# sheet1.net
KiCad netlist of a schematic drawn in Altium Designer
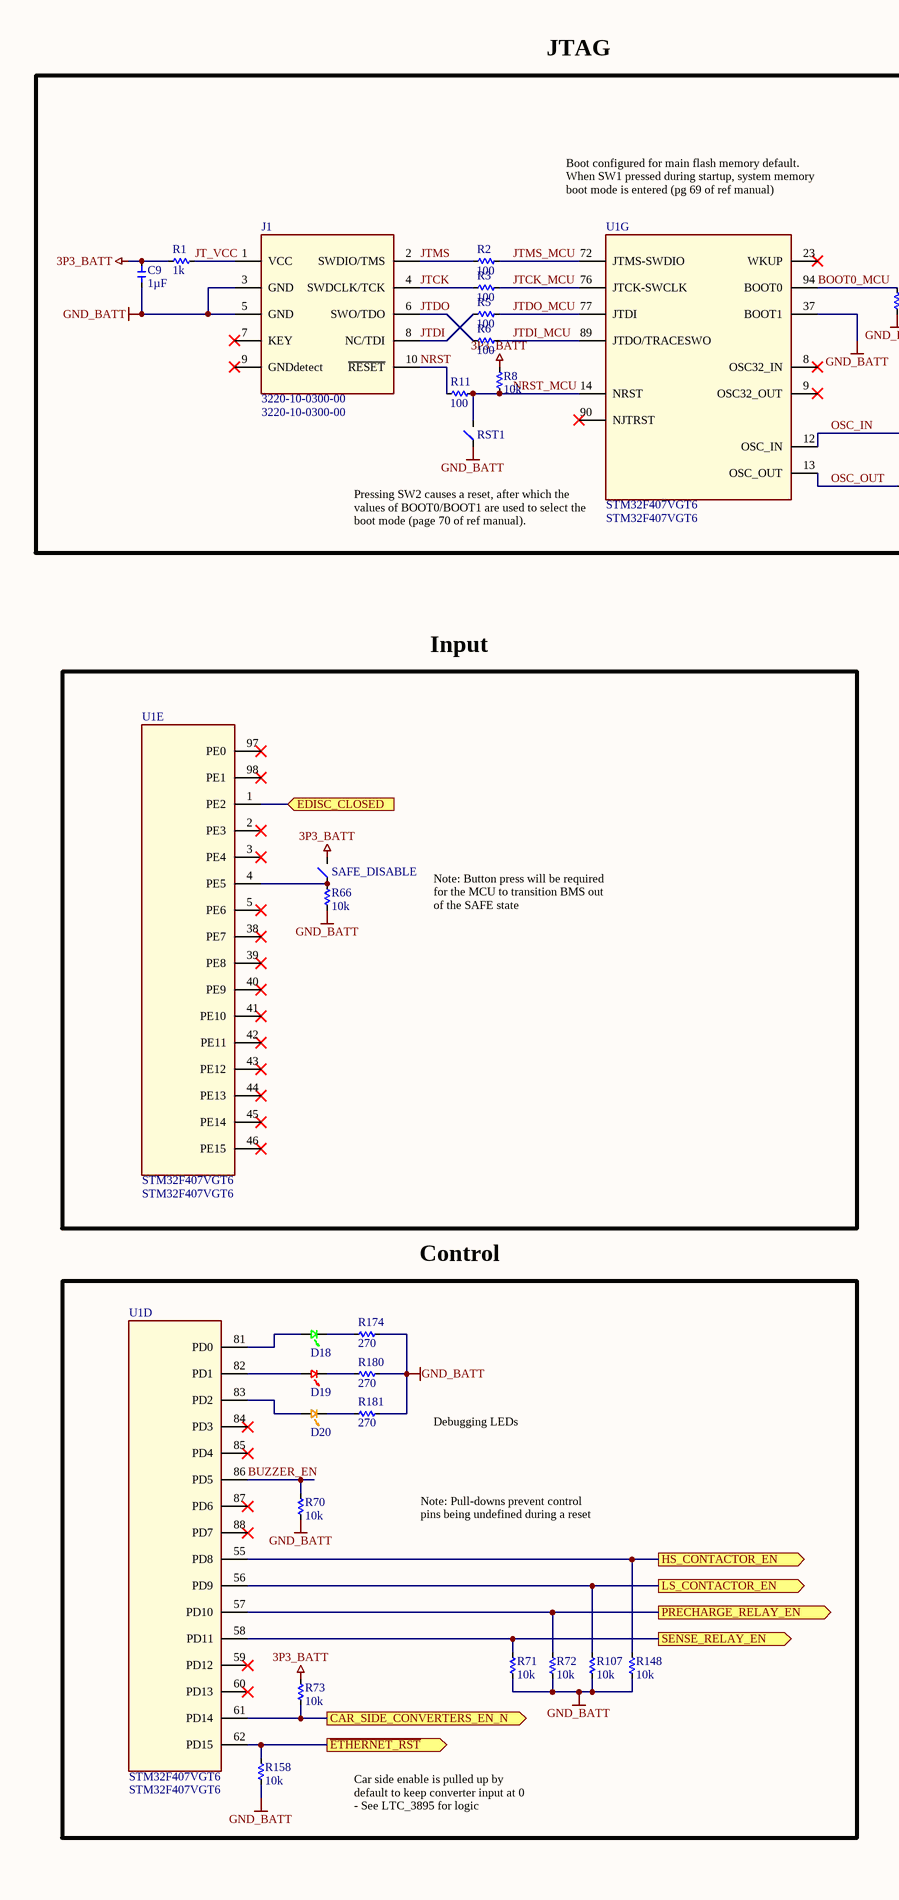
[diagram p0: sheet1.SchDoc, left]
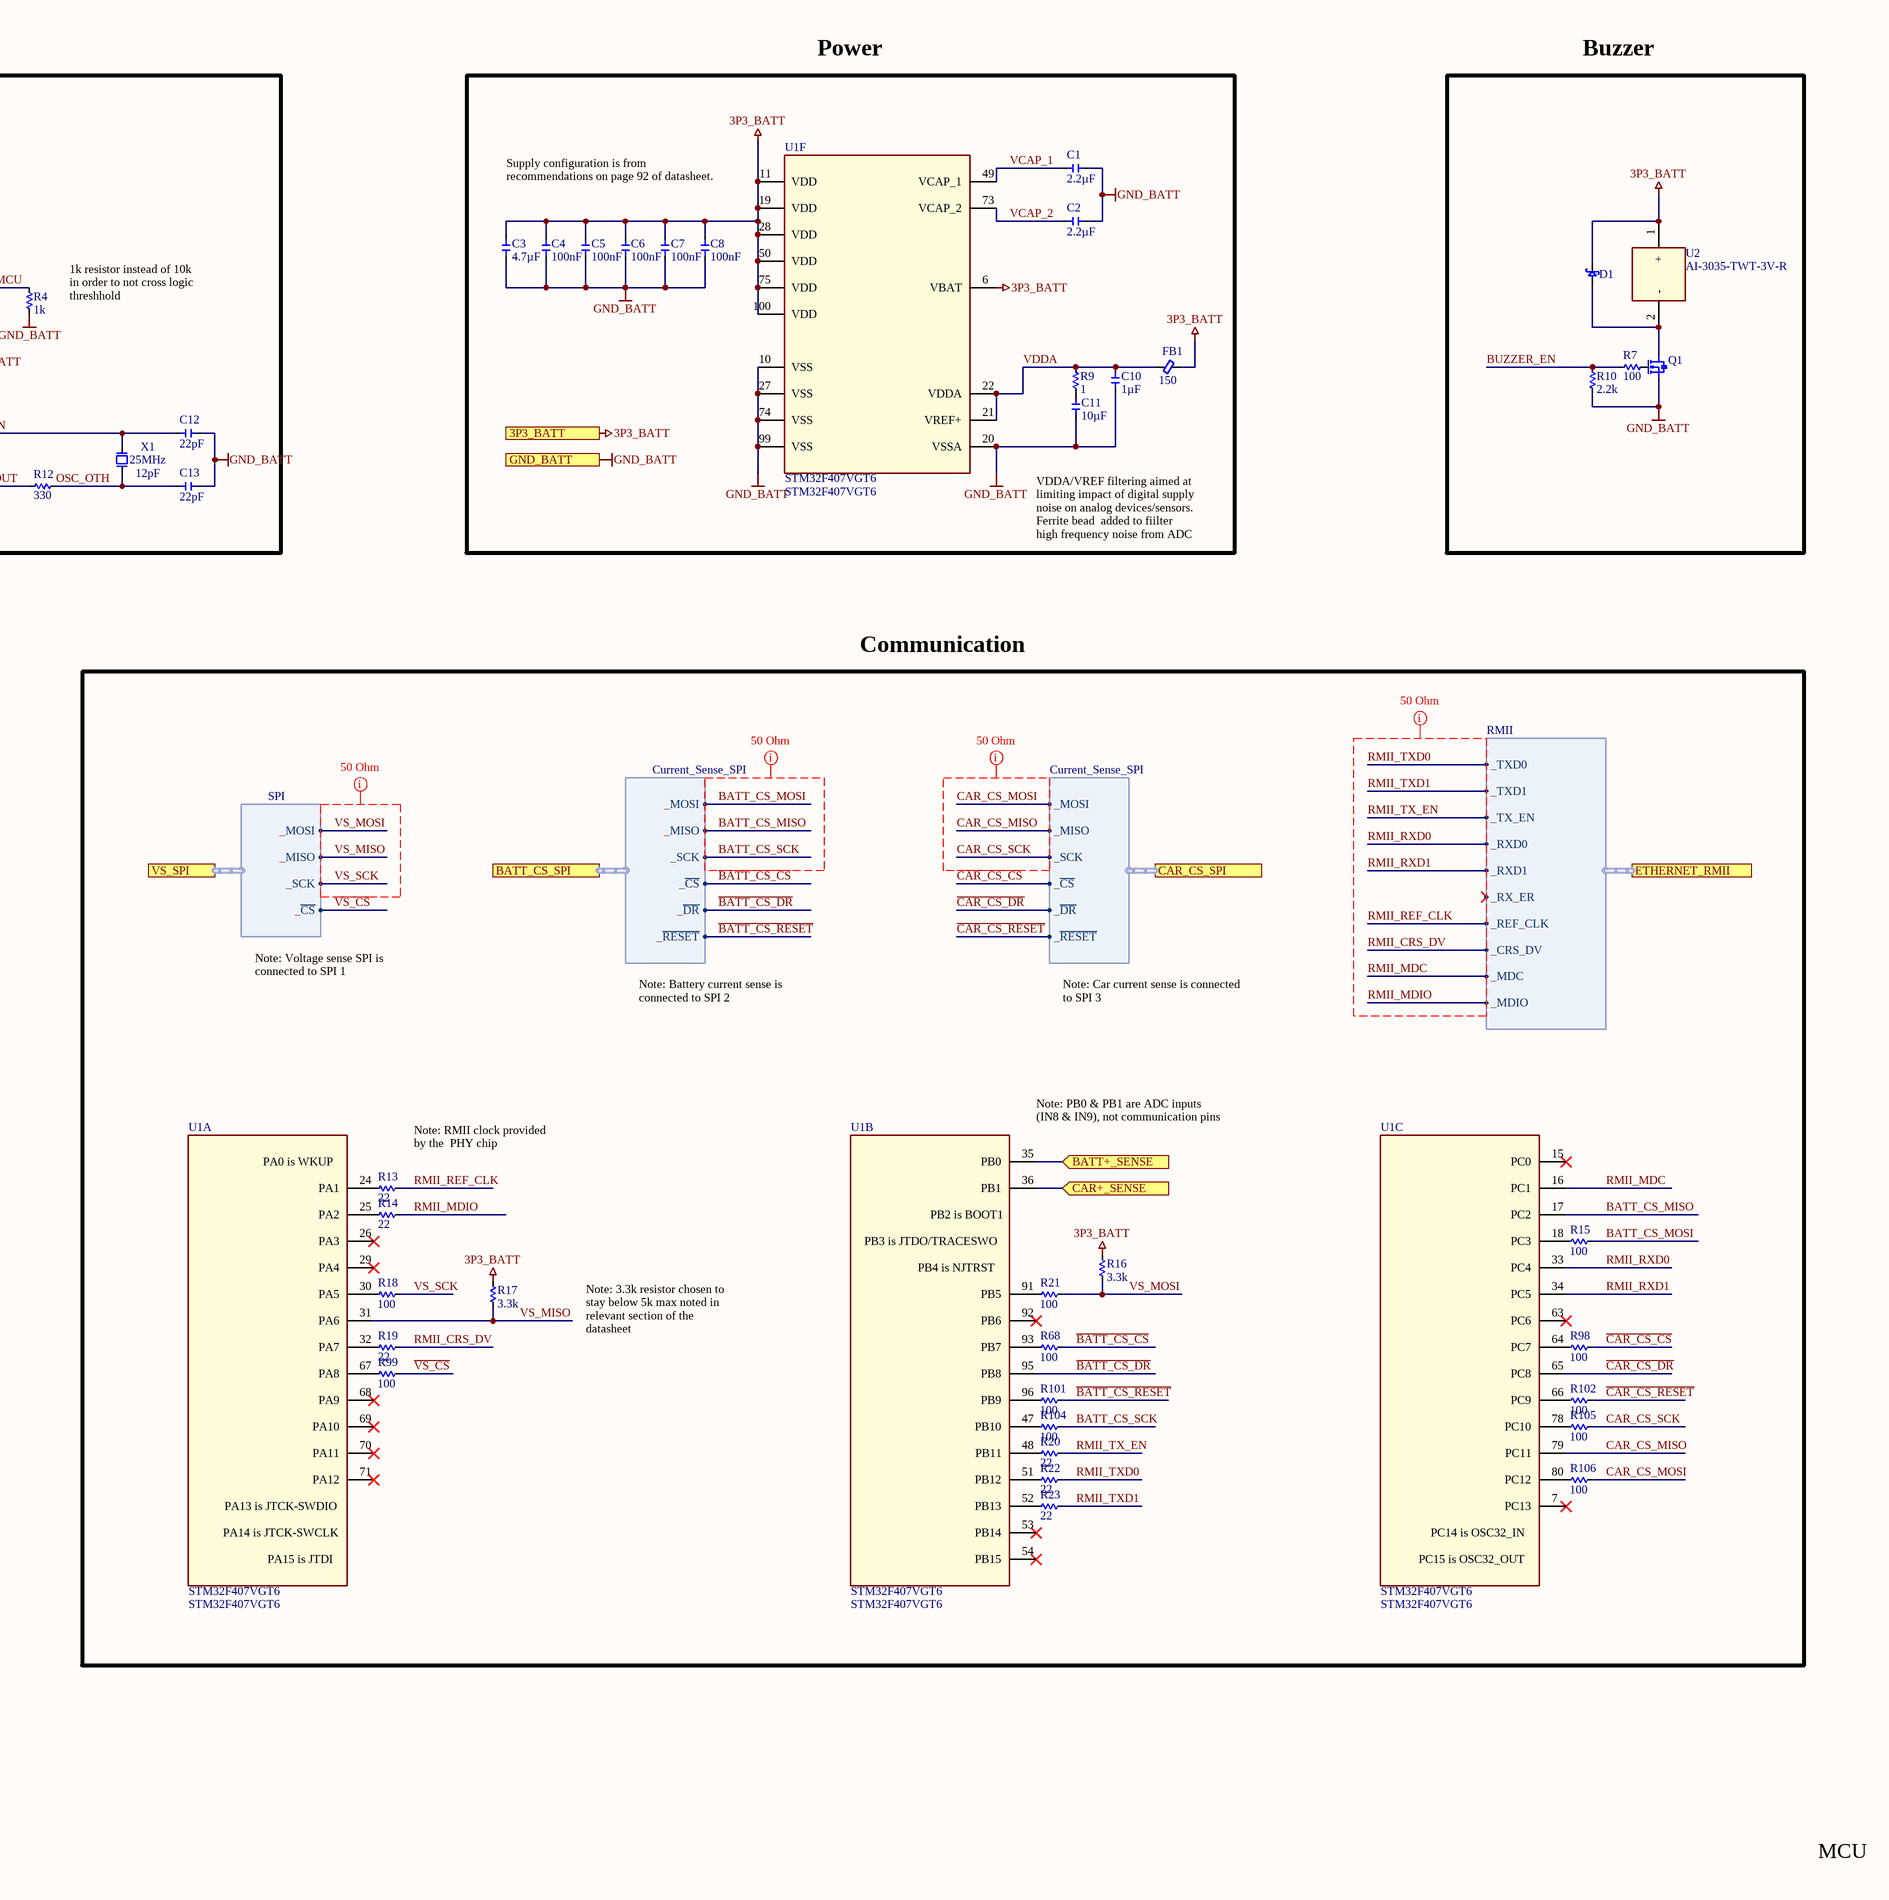
[diagram p1: sheet1.SchDoc, right]

(export (version "E")
  (design (tool "Eeschema 10.0.6"))
  (components
    (comp (ref "C1")
      (value "2.2µF")
      (footprint "C0603_0.90MM")
      (description "CAP CER 2.2UF 16V X7S 0603")
      (fields (field (name "TOLERANCE") "10%") (field (name "DIGI-KEY PART NUMBER") "445-16104-1-ND"))
      (libsource (lib "Stanford Solar Car Project") (part "2pin_nonpolar_capacitor"))
    )
    (comp (ref "C2")
      (value "2.2µF")
      (footprint "C0603_0.90MM")
      (description "CAP CER 2.2UF 16V X7S 0603")
      (fields (field (name "TOLERANCE") "10%") (field (name "DIGI-KEY PART NUMBER") "445-16104-1-ND"))
      (libsource (lib "Stanford Solar Car Project") (part "2pin_nonpolar_capacitor"))
    )
    (comp (ref "C3")
      (value "4.7µF")
      (footprint "C0805_1.45MM")
      (description "CAP CER 4.7UF 16V X7R 0805")
      (fields
        (field (name "MANUFACTURER") "TDK Corporation")
        (field (name "MANUFACTURER PART NUMBER") "CGA4J3X7R1C475K125AB")
      )
      (libsource (lib "Stanford Solar Car Project") (part "2pin_nonpolar_capacitor"))
    )
    (comp (ref "C4")
      (value "100nF")
      (footprint "C0603_0.90MM")
      (description "CAP CER 0.1UF 50V X7R 0603")
      (fields (field (name "DIGI-KEY PART NUMBER") "445-5666-1-ND") (field (name "TOLERANCE") "10%"))
      (libsource (lib "Stanford Solar Car Project") (part "2pin_nonpolar_capacitor"))
    )
    (comp (ref "C5")
      (value "100nF")
      (footprint "C0603_0.90MM")
      (description "CAP CER 0.1UF 50V X7R 0603")
      (fields (field (name "DIGI-KEY PART NUMBER") "445-5666-1-ND") (field (name "TOLERANCE") "10%"))
      (libsource (lib "Stanford Solar Car Project") (part "2pin_nonpolar_capacitor"))
    )
    (comp (ref "C6")
      (value "100nF")
      (footprint "C0603_0.90MM")
      (description "CAP CER 0.1UF 50V X7R 0603")
      (fields (field (name "DIGI-KEY PART NUMBER") "445-5666-1-ND") (field (name "TOLERANCE") "10%"))
      (libsource (lib "Stanford Solar Car Project") (part "2pin_nonpolar_capacitor"))
    )
    (comp (ref "C7")
      (value "100nF")
      (footprint "C0603_0.90MM")
      (description "CAP CER 0.1UF 50V X7R 0603")
      (fields (field (name "DIGI-KEY PART NUMBER") "445-5666-1-ND") (field (name "TOLERANCE") "10%"))
      (libsource (lib "Stanford Solar Car Project") (part "2pin_nonpolar_capacitor"))
    )
    (comp (ref "C8")
      (value "100nF")
      (footprint "C0603_0.90MM")
      (description "CAP CER 0.1UF 50V X7R 0603")
      (fields (field (name "DIGI-KEY PART NUMBER") "445-5666-1-ND") (field (name "TOLERANCE") "10%"))
      (libsource (lib "Stanford Solar Car Project") (part "2pin_nonpolar_capacitor"))
    )
    (comp (ref "C9")
      (value "1µF")
      (footprint "C0805_1.50MM")
      (description "CAP CER 1UF 50V X7R 0805")
      (fields
        (field (name "MANUFACTURER") "TDK Corporation")
        (field (name "DIGI-KEY PART NUMBER") "445-6961-1-ND")
      )
      (libsource (lib "Stanford Solar Car Project") (part "2pin_nonpolar_capacitor"))
    )
    (comp (ref "C10")
      (value "1µF")
      (footprint "C0805_1.50MM")
      (description "CAP CER 1UF 50V X7R 0805")
      (fields
        (field (name "MANUFACTURER") "TDK Corporation")
        (field (name "DIGI-KEY PART NUMBER") "445-6961-1-ND")
      )
      (libsource (lib "Stanford Solar Car Project") (part "2pin_nonpolar_capacitor"))
    )
    (comp (ref "C11")
      (value "10µF")
      (footprint "C1210_2.80MM")
      (description "CAP CER 10UF 25V X7R 1210")
      (fields
        (field (name "MANUFACTURER") "TDK Corporation")
        (field (name "MANUFACTURER PART NUMBER") "CGA6P1X7R1E106K250AC")
      )
      (libsource (lib "Stanford Solar Car Project") (part "2pin_nonpolar_capacitor"))
    )
    (comp (ref "C12")
      (value "22pF")
      (footprint "C0603_0.90MM")
      (description "CAP CER 22PF 50V C0G 0603")
      (fields (field (name "TOLERANCE") "5%") (field (name "DIGI-KEY PART NUMBER") "445-5632-1-ND"))
      (libsource (lib "Stanford Solar Car Project") (part "2pin_nonpolar_capacitor"))
    )
    (comp (ref "C13")
      (value "22pF")
      (footprint "C0603_0.90MM")
      (description "CAP CER 22PF 50V C0G 0603")
      (fields (field (name "TOLERANCE") "5%") (field (name "DIGI-KEY PART NUMBER") "445-5632-1-ND"))
      (libsource (lib "Stanford Solar Car Project") (part "2pin_nonpolar_capacitor"))
    )
    (comp (ref "D1")
      (value "DFLS130L-7")
      (footprint "DIOD-POWERDI123-2_A_V")
      (libsource (lib "Stanford Solar Car Project") (part "_template_schottky"))
    )
    (comp (ref "D18")
      (value "LTST-C191KGKT")
      (footprint "LED_0603P_GREEN")
      (description "LED GREEN CLEAR SMD")
      (fields
        (field (name "MANUFACTURER") "Lite-On Inc.")
        (field (name "DIGI-KEY PART NUMBER") "160-1446-6-ND")
      )
      (libsource (lib "Stanford Solar Car Project") (part "_template_led_green"))
    )
    (comp (ref "D19")
      (value "LTST-C194KRKT")
      (footprint "LED_0603P_RED")
      (description "LED RED CLEAR SMD")
      (fields
        (field (name "DIGI-KEY PART NUMBER") "160-1835-6-ND")
        (field (name "MANUFACTURER") "Lite-On Inc.")
      )
      (libsource (lib "Stanford Solar Car Project") (part "_template_led_red"))
    )
    (comp (ref "D20")
      (value "LTST-C194KFKT")
      (footprint "LED_0603P_ORANGE")
      (description "LED ORANGE CLEAR SMD")
      (libsource (lib "Stanford Solar Car Project") (part "_template_led_orange"))
    )
    (comp (ref "FB1")
      (value "MPZ1608Y151BTD25")
      (footprint "FB0603_0.95MM")
      (description "FERRITE BEAD 150 OHM 0603 1LN")
      (fields
        (field (name "DIGI-KEY PART NUMBER") "445-172900-1-ND")
        (field (name "IMPEDANCE (OHMS @ 100MHZ)") "150")
        (field (name "MANUFACTURER") "TDK Corporation")
      )
      (libsource (lib "Stanford Solar Car Project") (part "2pin_ferritebead"))
    )
    (comp (ref "J1")
      (value "3220-10-0300-00")
      (footprint "3220-10-0300-00")
      (description "CONN HEADER SMD 10POS 1.27MM")
      (fields
        (field (name "MANUFACTURER PART NUMBER") "3220-10-0300-00")
        (field (name "MANUFACTURER") "CNC Tech")
        (field (name "DIGI-KEY PART NUMBER") "1175-1629-ND")
      )
      (libsource (lib "Stanford Solar Car Project") (part "CONN_3220-10-0300-00"))
    )
    (comp (ref "Q1")
      (value "BSR802NL6327")
      (footprint "3SOT23")
      (description "Infineon BSR802N L6327 N-channel MOSFET Transistor, 3.7 A, 20 V, 3-Pin SC-59")
      (libsource (lib "Stanford Solar Car Project") (part "__template_nfet"))
    )
    (comp (ref "R1")
      (value "1k")
      (footprint "R0603_0.55MM")
      (description "RES SMD 1K OHM 1% 1/4W 0603")
      (fields (field (name "TOLERANCE") "1%") (field (name "DIGI-KEY PART NUMBER") "P1.0KBYCT-ND"))
      (libsource (lib "Stanford Solar Car Project") (part "2pin_resistor"))
    )
    (comp (ref "R2")
      (value "100")
      (footprint "R0603_0.55MM")
      (description "RES SMD 100 OHM 1% 1/10W 0603")
      (fields
        (field (name "MANUFACTURER PART NUMBER") "ERJ-3EKF1000V")
        (field (name "DIGI-KEY PART NUMBER") "P100HCT-ND")
      )
      (libsource (lib "Stanford Solar Car Project") (part "2pin_resistor"))
    )
    (comp (ref "R3")
      (value "100")
      (footprint "R0603_0.55MM")
      (description "RES SMD 100 OHM 1% 1/10W 0603")
      (fields
        (field (name "MANUFACTURER PART NUMBER") "ERJ-3EKF1000V")
        (field (name "DIGI-KEY PART NUMBER") "P100HCT-ND")
      )
      (libsource (lib "Stanford Solar Car Project") (part "2pin_resistor"))
    )
    (comp (ref "R4")
      (value "1k")
      (footprint "R0603_0.55MM")
      (description "RES SMD 1K OHM 1% 1/4W 0603")
      (fields (field (name "TOLERANCE") "1%") (field (name "DIGI-KEY PART NUMBER") "P1.0KBYCT-ND"))
      (libsource (lib "Stanford Solar Car Project") (part "2pin_resistor"))
    )
    (comp (ref "R5")
      (value "100")
      (footprint "R0603_0.55MM")
      (description "RES SMD 100 OHM 1% 1/10W 0603")
      (fields
        (field (name "MANUFACTURER PART NUMBER") "ERJ-3EKF1000V")
        (field (name "DIGI-KEY PART NUMBER") "P100HCT-ND")
      )
      (libsource (lib "Stanford Solar Car Project") (part "2pin_resistor"))
    )
    (comp (ref "R6")
      (value "100")
      (footprint "R0603_0.55MM")
      (description "RES SMD 100 OHM 1% 1/10W 0603")
      (fields
        (field (name "MANUFACTURER PART NUMBER") "ERJ-3EKF1000V")
        (field (name "DIGI-KEY PART NUMBER") "P100HCT-ND")
      )
      (libsource (lib "Stanford Solar Car Project") (part "2pin_resistor"))
    )
    (comp (ref "R7")
      (value "100")
      (footprint "R0603_0.55MM")
      (description "RES SMD 100 OHM 1% 1/4W 0603")
      (fields (field (name "MANUFACTURER PART NUMBER") "ERJ-PA3F1000V") (field (name "TOLERANCE") "1%"))
      (libsource (lib "Stanford Solar Car Project") (part "2pin_resistor"))
    )
    (comp (ref "R8")
      (value "10k")
      (footprint "R0603_0.55MM")
      (description "RES SMD 10K OHM 1% 1/10W 0603")
      (fields
        (field (name "MANUFACTURER PART NUMBER") "ERJ-3EKF1002V")
        (field (name "MANUFACTURER") "Panasonic Electronic Components")
      )
      (libsource (lib "Stanford Solar Car Project") (part "2pin_resistor"))
    )
    (comp (ref "R9")
      (value "1")
      (footprint "R0603_0.55MM")
      (description "RES SMD 1 OHM 1% 1/10W 0603")
      (fields (field (name "TOLERANCE") "1%") (field (name "DIGI-KEY PART NUMBER") "P1.0AJCT-ND"))
      (libsource (lib "Stanford Solar Car Project") (part "2pin_resistor"))
    )
    (comp (ref "R10")
      (value "2.2k")
      (footprint "R0603_0.55MM")
      (description "RES SMD 2.2K OHM 1% 1/4W 0603")
      (fields (field (name "MANUFACTURER") "Panasonic Electronic Components") (field (name "TOLERANCE") "1%"))
      (libsource (lib "Stanford Solar Car Project") (part "2pin_resistor"))
    )
    (comp (ref "R11")
      (value "100")
      (footprint "R0603_0.55MM")
      (description "RES SMD 100 OHM 1% 1/10W 0603")
      (fields
        (field (name "MANUFACTURER PART NUMBER") "ERJ-3EKF1000V")
        (field (name "DIGI-KEY PART NUMBER") "P100HCT-ND")
      )
      (libsource (lib "Stanford Solar Car Project") (part "2pin_resistor"))
    )
    (comp (ref "R12")
      (value "330")
      (footprint "R0603_0.55MM")
      (description "RES SMD 330 OHM 1% 1/10W 0603")
      (fields
        (field (name "DIGI-KEY PART NUMBER") "P330HCT-ND")
        (field (name "MANUFACTURER PART NUMBER") "ERJ-3EKF3300V")
      )
      (libsource (lib "Stanford Solar Car Project") (part "2pin_resistor"))
    )
    (comp (ref "R13")
      (value "22")
      (footprint "R0603_0.55MM")
      (description "RES SMD 22 OHM 1% 1/10W 0603")
      (fields
        (field (name "MANUFACTURER") "Panasonic Electronic Components")
        (field (name "DIGI-KEY PART NUMBER") "P22.0HCT-ND")
      )
      (libsource (lib "Stanford Solar Car Project") (part "2pin_resistor"))
    )
    (comp (ref "R14")
      (value "22")
      (footprint "R0603_0.55MM")
      (description "RES SMD 22 OHM 1% 1/10W 0603")
      (fields
        (field (name "MANUFACTURER") "Panasonic Electronic Components")
        (field (name "DIGI-KEY PART NUMBER") "P22.0HCT-ND")
      )
      (libsource (lib "Stanford Solar Car Project") (part "2pin_resistor"))
    )
    (comp (ref "R15")
      (value "100")
      (footprint "R0603_0.55MM")
      (description "RES SMD 100 OHM 1% 1/10W 0603")
      (fields
        (field (name "MANUFACTURER PART NUMBER") "ERJ-3EKF1000V")
        (field (name "DIGI-KEY PART NUMBER") "P100HCT-ND")
      )
      (libsource (lib "Stanford Solar Car Project") (part "2pin_resistor"))
    )
    (comp (ref "R16")
      (value "3.3k")
      (footprint "R0603_0.55MM")
      (description "RES SMD 3.3K OHM 1% 1/10W 0603")
      (fields
        (field (name "DIGI-KEY PART NUMBER") "P3.30KHCT-ND")
        (field (name "MANUFACTURER") "Panasonic Electronic Components")
      )
      (libsource (lib "Stanford Solar Car Project") (part "2pin_resistor"))
    )
    (comp (ref "R17")
      (value "3.3k")
      (footprint "R0603_0.55MM")
      (description "RES SMD 3.3K OHM 1% 1/10W 0603")
      (fields
        (field (name "DIGI-KEY PART NUMBER") "P3.30KHCT-ND")
        (field (name "MANUFACTURER") "Panasonic Electronic Components")
      )
      (libsource (lib "Stanford Solar Car Project") (part "2pin_resistor"))
    )
    (comp (ref "R18")
      (value "100")
      (footprint "R0603_0.55MM")
      (description "RES SMD 100 OHM 1% 1/10W 0603")
      (fields
        (field (name "MANUFACTURER PART NUMBER") "ERJ-3EKF1000V")
        (field (name "DIGI-KEY PART NUMBER") "P100HCT-ND")
      )
      (libsource (lib "Stanford Solar Car Project") (part "2pin_resistor"))
    )
    (comp (ref "R19")
      (value "22")
      (footprint "R0603_0.55MM")
      (description "RES SMD 22 OHM 1% 1/10W 0603")
      (fields
        (field (name "MANUFACTURER") "Panasonic Electronic Components")
        (field (name "DIGI-KEY PART NUMBER") "P22.0HCT-ND")
      )
      (libsource (lib "Stanford Solar Car Project") (part "2pin_resistor"))
    )
    (comp (ref "R20")
      (value "22")
      (footprint "R0603_0.55MM")
      (description "RES SMD 22 OHM 1% 1/10W 0603")
      (fields
        (field (name "MANUFACTURER") "Panasonic Electronic Components")
        (field (name "DIGI-KEY PART NUMBER") "P22.0HCT-ND")
      )
      (libsource (lib "Stanford Solar Car Project") (part "2pin_resistor"))
    )
    (comp (ref "R21")
      (value "100")
      (footprint "R0603_0.55MM")
      (description "RES SMD 100 OHM 1% 1/10W 0603")
      (fields
        (field (name "MANUFACTURER PART NUMBER") "ERJ-3EKF1000V")
        (field (name "DIGI-KEY PART NUMBER") "P100HCT-ND")
      )
      (libsource (lib "Stanford Solar Car Project") (part "2pin_resistor"))
    )
    (comp (ref "R22")
      (value "22")
      (footprint "R0603_0.55MM")
      (description "RES SMD 22 OHM 1% 1/10W 0603")
      (fields
        (field (name "MANUFACTURER") "Panasonic Electronic Components")
        (field (name "DIGI-KEY PART NUMBER") "P22.0HCT-ND")
      )
      (libsource (lib "Stanford Solar Car Project") (part "2pin_resistor"))
    )
    (comp (ref "R23")
      (value "22")
      (footprint "R0603_0.55MM")
      (description "RES SMD 22 OHM 1% 1/10W 0603")
      (fields
        (field (name "MANUFACTURER") "Panasonic Electronic Components")
        (field (name "DIGI-KEY PART NUMBER") "P22.0HCT-ND")
      )
      (libsource (lib "Stanford Solar Car Project") (part "2pin_resistor"))
    )
    (comp (ref "R66")
      (value "10k")
      (footprint "R0603_0.55MM")
      (description "RES SMD 10K OHM 1% 1/10W 0603")
      (fields
        (field (name "MANUFACTURER PART NUMBER") "ERJ-3EKF1002V")
        (field (name "MANUFACTURER") "Panasonic Electronic Components")
      )
      (libsource (lib "Stanford Solar Car Project") (part "2pin_resistor"))
    )
    (comp (ref "R68")
      (value "100")
      (footprint "R0603_0.55MM")
      (description "RES SMD 100 OHM 1% 1/10W 0603")
      (fields
        (field (name "MANUFACTURER PART NUMBER") "ERJ-3EKF1000V")
        (field (name "DIGI-KEY PART NUMBER") "P100HCT-ND")
      )
      (libsource (lib "Stanford Solar Car Project") (part "2pin_resistor"))
    )
    (comp (ref "R70")
      (value "10k")
      (footprint "R0603_0.55MM")
      (description "RES SMD 10K OHM 1% 1/10W 0603")
      (fields
        (field (name "MANUFACTURER PART NUMBER") "ERJ-3EKF1002V")
        (field (name "MANUFACTURER") "Panasonic Electronic Components")
      )
      (libsource (lib "Stanford Solar Car Project") (part "2pin_resistor"))
    )
    (comp (ref "R71")
      (value "10k")
      (footprint "R0603_0.55MM")
      (description "RES SMD 10K OHM 1% 1/10W 0603")
      (fields
        (field (name "MANUFACTURER PART NUMBER") "ERJ-3EKF1002V")
        (field (name "MANUFACTURER") "Panasonic Electronic Components")
      )
      (libsource (lib "Stanford Solar Car Project") (part "2pin_resistor"))
    )
    (comp (ref "R72")
      (value "10k")
      (footprint "R0603_0.55MM")
      (description "RES SMD 10K OHM 1% 1/10W 0603")
      (fields
        (field (name "MANUFACTURER PART NUMBER") "ERJ-3EKF1002V")
        (field (name "MANUFACTURER") "Panasonic Electronic Components")
      )
      (libsource (lib "Stanford Solar Car Project") (part "2pin_resistor"))
    )
    (comp (ref "R73")
      (value "10k")
      (footprint "R0603_0.55MM")
      (description "RES SMD 10K OHM 1% 1/10W 0603")
      (fields
        (field (name "MANUFACTURER PART NUMBER") "ERJ-3EKF1002V")
        (field (name "MANUFACTURER") "Panasonic Electronic Components")
      )
      (libsource (lib "Stanford Solar Car Project") (part "2pin_resistor"))
    )
    (comp (ref "R98")
      (value "100")
      (footprint "R0603_0.55MM")
      (description "RES SMD 100 OHM 1% 1/10W 0603")
      (fields
        (field (name "MANUFACTURER PART NUMBER") "ERJ-3EKF1000V")
        (field (name "DIGI-KEY PART NUMBER") "P100HCT-ND")
      )
      (libsource (lib "Stanford Solar Car Project") (part "2pin_resistor"))
    )
    (comp (ref "R99")
      (value "100")
      (footprint "R0603_0.55MM")
      (description "RES SMD 100 OHM 1% 1/10W 0603")
      (fields
        (field (name "MANUFACTURER PART NUMBER") "ERJ-3EKF1000V")
        (field (name "DIGI-KEY PART NUMBER") "P100HCT-ND")
      )
      (libsource (lib "Stanford Solar Car Project") (part "2pin_resistor"))
    )
    (comp (ref "R101")
      (value "100")
      (footprint "R0603_0.55MM")
      (description "RES SMD 100 OHM 1% 1/10W 0603")
      (fields
        (field (name "MANUFACTURER PART NUMBER") "ERJ-3EKF1000V")
        (field (name "DIGI-KEY PART NUMBER") "P100HCT-ND")
      )
      (libsource (lib "Stanford Solar Car Project") (part "2pin_resistor"))
    )
    (comp (ref "R102")
      (value "100")
      (footprint "R0603_0.55MM")
      (description "RES SMD 100 OHM 1% 1/10W 0603")
      (fields
        (field (name "MANUFACTURER PART NUMBER") "ERJ-3EKF1000V")
        (field (name "DIGI-KEY PART NUMBER") "P100HCT-ND")
      )
      (libsource (lib "Stanford Solar Car Project") (part "2pin_resistor"))
    )
    (comp (ref "R104")
      (value "100")
      (footprint "R0603_0.55MM")
      (description "RES SMD 100 OHM 1% 1/10W 0603")
      (fields
        (field (name "MANUFACTURER PART NUMBER") "ERJ-3EKF1000V")
        (field (name "DIGI-KEY PART NUMBER") "P100HCT-ND")
      )
      (libsource (lib "Stanford Solar Car Project") (part "2pin_resistor"))
    )
    (comp (ref "R105")
      (value "100")
      (footprint "R0603_0.55MM")
      (description "RES SMD 100 OHM 1% 1/10W 0603")
      (fields
        (field (name "MANUFACTURER PART NUMBER") "ERJ-3EKF1000V")
        (field (name "DIGI-KEY PART NUMBER") "P100HCT-ND")
      )
      (libsource (lib "Stanford Solar Car Project") (part "2pin_resistor"))
    )
    (comp (ref "R106")
      (value "100")
      (footprint "R0603_0.55MM")
      (description "RES SMD 100 OHM 1% 1/10W 0603")
      (fields
        (field (name "MANUFACTURER PART NUMBER") "ERJ-3EKF1000V")
        (field (name "DIGI-KEY PART NUMBER") "P100HCT-ND")
      )
      (libsource (lib "Stanford Solar Car Project") (part "2pin_resistor"))
    )
    (comp (ref "R107")
      (value "10k")
      (footprint "R0603_0.55MM")
      (description "RES SMD 10K OHM 1% 1/10W 0603")
      (fields
        (field (name "MANUFACTURER PART NUMBER") "ERJ-3EKF1002V")
        (field (name "MANUFACTURER") "Panasonic Electronic Components")
      )
      (libsource (lib "Stanford Solar Car Project") (part "2pin_resistor"))
    )
    (comp (ref "R148")
      (value "10k")
      (footprint "R0603_0.55MM")
      (description "RES SMD 10K OHM 1% 1/10W 0603")
      (fields
        (field (name "MANUFACTURER PART NUMBER") "ERJ-3EKF1002V")
        (field (name "MANUFACTURER") "Panasonic Electronic Components")
      )
      (libsource (lib "Stanford Solar Car Project") (part "2pin_resistor"))
    )
    (comp (ref "R158")
      (value "10k")
      (footprint "R0603_0.55MM")
      (description "RES SMD 10K OHM 1% 1/10W 0603")
      (fields
        (field (name "MANUFACTURER PART NUMBER") "ERJ-3EKF1002V")
        (field (name "MANUFACTURER") "Panasonic Electronic Components")
      )
      (libsource (lib "Stanford Solar Car Project") (part "2pin_resistor"))
    )
    (comp (ref "R174")
      (value "270")
      (footprint "R0603_0.55MM")
      (description "RES SMD 270 OHM 1% 1/4W 0603")
      (fields (field (name "TOLERANCE") "1%") (field (name "DIGI-KEY PART NUMBER") "P270BYCT-ND"))
      (libsource (lib "Stanford Solar Car Project") (part "2pin_resistor"))
    )
    (comp (ref "R180")
      (value "270")
      (footprint "R0603_0.55MM")
      (description "RES SMD 270 OHM 1% 1/4W 0603")
      (fields (field (name "TOLERANCE") "1%") (field (name "DIGI-KEY PART NUMBER") "P270BYCT-ND"))
      (libsource (lib "Stanford Solar Car Project") (part "2pin_resistor"))
    )
    (comp (ref "R181")
      (value "270")
      (footprint "R0603_0.55MM")
      (description "RES SMD 270 OHM 1% 1/4W 0603")
      (fields (field (name "TOLERANCE") "1%") (field (name "DIGI-KEY PART NUMBER") "P270BYCT-ND"))
      (libsource (lib "Stanford Solar Car Project") (part "2pin_resistor"))
    )
    (comp (ref "RST1")
      (value "B3U-1000P")
      (footprint "SWITCH_B3U-1000P")
      (description "SWITCH TACTILE SPST-NO 0.05A 12V")
      (fields
        (field (name "DIGI-KEY PART NUMBER") "SW1020CT-ND")
        (field (name "MANUFACTURER") "Omron Electronics Inc-EMC Div")
      )
      (libsource (lib "Stanford Solar Car Project") (part "_generic_spst-no"))
    )
    (comp (ref "SAFE_DISABLE")
      (value "B3U-1000P")
      (footprint "SWITCH_B3U-1000P")
      (description "SWITCH TACTILE SPST-NO 0.05A 12V")
      (fields
        (field (name "DIGI-KEY PART NUMBER") "SW1020CT-ND")
        (field (name "MANUFACTURER") "Omron Electronics Inc-EMC Div")
      )
      (libsource (lib "Stanford Solar Car Project") (part "_generic_spst-no"))
    )
    (comp (ref "U1")
      (value "STM32F407VGT6")
      (footprint "QFP50P1600X1600X160-100N")
      (description "MCU 32-bit STM32F ARM Cortex M4F RISC 1024KB Flash 2.5V/3.3V 100-Pin LQFP Tray")
      (fields
        (field (name "MANUFACTURER PART NUMBER") "STM32F407VGT6")
        (field (name "MANUFACTURER") "STMicroelectronics")
      )
      (libsource (lib "Stanford Solar Car Project") (part "MCU_STM32F427VGT7"))
    )
    (comp (ref "U2")
      (value "AI-3035-TWT-3V-R")
      (footprint "New footprint 1")
      (description "Audio Indicator Indicator Piezo 3Vdc 9mA Pin 2Vdc 3000Hz to 4000Hz Through Hole")
      (fields (field (name "MANUFACTURER") "Projects Unlimited"))
      (libsource (lib "Stanford Solar Car Project") (part "New symbol 1"))
    )
    (comp (ref "X1")
      (value "CX2016DB25000H0FLJC1")
      (footprint "4_SMD_2.0x1.6mm")
      (description "CRYSTAL 25.0000MHZ 12PF SMD")
      (fields
        (field (name "LOAD CAPACITANCE") "12pF")
        (field (name "FREQUENCY") "25MHz")
        (field (name "DIGI-KEY PART NUMBER") "1253-1709-1-ND")
        (field (name "MANUFACTURER") "Kyocera International Inc. Electronic Components")
      )
      (libsource (lib "Stanford Solar Car Project") (part "OSC_25MHZ_CRYSTAL"))
    )
  )
  (nets
    (net (code "4") (name "/BATT+_SENSE") (class "Default")
      (node (ref "U1") (pin "35") (pinfunction "PB0_35") (pintype "passive"))
    )
    (net (code "5") (name "/BATT_CS_MISO") (class "Default")
      (node (ref "U1") (pin "17") (pinfunction "PC2_17") (pintype "passive"))
    )
    (net (code "6") (name "/BATT_CS_MOSI") (class "Default") (node (ref "R15") (pin "2") (pintype "passive")))
    (net (code "7") (name "/BATT_CS_SCK") (class "Default") (node (ref "R104") (pin "2") (pintype "passive")))
    (net (code "8") (name "/BOOT0_MCU") (class "Default")
      (node (ref "R4") (pin "1") (pintype "passive"))
      (node (ref "U1") (pin "94") (pinfunction "BOOT0_94") (pintype "passive"))
    )
    (net (code "9") (name "/BUZZER_EN") (class "Default")
      (node (ref "R10") (pin "1") (pintype "passive"))
      (node (ref "R7") (pin "1") (pintype "passive"))
      (node (ref "R70") (pin "1") (pintype "passive"))
      (node (ref "U1") (pin "86") (pinfunction "PD5_86") (pintype "passive"))
    )
    (net (code "10") (name "/CAR+_SENSE") (class "Default")
      (node (ref "U1") (pin "36") (pinfunction "PB1_36") (pintype "passive"))
    )
    (net (code "11") (name "/CAR_CS_MISO") (class "Default")
      (node (ref "U1") (pin "79") (pinfunction "PC11_79") (pintype "passive"))
    )
    (net (code "12") (name "/CAR_CS_MOSI") (class "Default")
      (node (ref "R106") (pin "2") (pintype "passive"))
    )
    (net (code "13") (name "/CAR_CS_SCK") (class "Default") (node (ref "R105") (pin "2") (pintype "passive")))
    (net (code "14") (name "/CAR_SIDE_CONVERTERS_EN_N") (class "Default")
      (node (ref "R73") (pin "2") (pintype "passive"))
      (node (ref "U1") (pin "61") (pinfunction "PD14_61") (pintype "passive"))
    )
    (net (code "15") (name "/EDISC_CLOSED") (class "Default")
      (node (ref "U1") (pin "1") (pinfunction "PE2_1") (pintype "passive"))
    )
    (net (code "16") (name "/HS_CONTACTOR_EN") (class "Default")
      (node (ref "R148") (pin "1") (pintype "passive"))
      (node (ref "U1") (pin "55") (pinfunction "PD8_55") (pintype "passive"))
    )
    (net (code "17") (name "/JTCK") (class "Default")
      (node (ref "J1") (pin "4") (pinfunction "SWDCLK/TCK_4") (pintype "passive"))
      (node (ref "R3") (pin "1") (pintype "passive"))
    )
    (net (code "18") (name "/JTCK_MCU") (class "Default")
      (node (ref "R3") (pin "2") (pintype "passive"))
      (node (ref "U1") (pin "76") (pinfunction "JTCK-SWCLK_76") (pintype "passive"))
    )
    (net (code "19") (name "/JTDI") (class "Default")
      (node (ref "J1") (pin "8") (pinfunction "NC/TDI_8") (pintype "passive"))
      (node (ref "R5") (pin "1") (pintype "passive"))
    )
    (net (code "20") (name "/JTDI_MCU") (class "Default")
      (node (ref "R6") (pin "2") (pintype "passive"))
      (node (ref "U1") (pin "89") (pinfunction "JTDO/TRACESWO_89") (pintype "passive"))
    )
    (net (code "21") (name "/JTDO") (class "Default")
      (node (ref "J1") (pin "6") (pinfunction "SWO/TDO_6") (pintype "passive"))
      (node (ref "R6") (pin "1") (pintype "passive"))
    )
    (net (code "22") (name "/JTDO_MCU") (class "Default")
      (node (ref "R5") (pin "2") (pintype "passive"))
      (node (ref "U1") (pin "77") (pinfunction "JTDI_77") (pintype "passive"))
    )
    (net (code "23") (name "/JTMS") (class "Default")
      (node (ref "J1") (pin "2") (pinfunction "SWDIO/TMS_2") (pintype "passive"))
      (node (ref "R2") (pin "1") (pintype "passive"))
    )
    (net (code "24") (name "/JTMS_MCU") (class "Default")
      (node (ref "R2") (pin "2") (pintype "passive"))
      (node (ref "U1") (pin "72") (pinfunction "JTMS-SWDIO_72") (pintype "passive"))
    )
    (net (code "25") (name "/JT_VCC") (class "Default")
      (node (ref "J1") (pin "1") (pinfunction "VCC_1") (pintype "passive"))
      (node (ref "R1") (pin "2") (pintype "passive"))
    )
    (net (code "26") (name "/LS_CONTACTOR_EN") (class "Default")
      (node (ref "R107") (pin "1") (pintype "passive"))
      (node (ref "U1") (pin "56") (pinfunction "PD9_56") (pintype "passive"))
    )
    (net (code "27") (name "/NRST") (class "Default")
      (node (ref "J1") (pin "10") (pinfunction "~{RESET}_10") (pintype "passive"))
      (node (ref "R11") (pin "1") (pintype "passive"))
    )
    (net (code "28") (name "/NRST_MCU") (class "Default")
      (node (ref "R11") (pin "2") (pintype "passive"))
      (node (ref "R8") (pin "2") (pintype "passive"))
      (node (ref "RST1") (pin "2") (pintype "passive"))
      (node (ref "U1") (pin "14") (pinfunction "NRST_14") (pintype "passive"))
    )
    (net (code "29") (name "/OSC_IN") (class "Default")
      (node (ref "C12") (pin "1") (pintype "passive"))
      (node (ref "U1") (pin "12") (pinfunction "OSC_IN_12") (pintype "passive"))
      (node (ref "X1") (pin "3") (pinfunction "3_3") (pintype "passive"))
    )
    (net (code "30") (name "/OSC_OTH") (class "Default")
      (node (ref "C13") (pin "1") (pintype "passive"))
      (node (ref "R12") (pin "2") (pintype "passive"))
      (node (ref "X1") (pin "1") (pinfunction "1_1") (pintype "passive"))
    )
    (net (code "31") (name "/OSC_OUT") (class "Default")
      (node (ref "R12") (pin "1") (pintype "passive"))
      (node (ref "U1") (pin "13") (pinfunction "OSC_OUT_13") (pintype "passive"))
    )
    (net (code "32") (name "/PRECHARGE_RELAY_EN") (class "Default")
      (node (ref "R72") (pin "1") (pintype "passive"))
      (node (ref "U1") (pin "57") (pinfunction "PD10_57") (pintype "passive"))
    )
    (net (code "33") (name "/RMII_CRS_DV") (class "Default") (node (ref "R19") (pin "1") (pintype "passive")))
    (net (code "34") (name "/RMII_MDC") (class "Default")
      (node (ref "U1") (pin "16") (pinfunction "PC1_16") (pintype "passive"))
    )
    (net (code "35") (name "/RMII_MDIO") (class "Default") (node (ref "R14") (pin "1") (pintype "passive")))
    (net (code "36") (name "/RMII_REF_CLK") (class "Default")
      (node (ref "R13") (pin "1") (pintype "passive"))
    )
    (net (code "37") (name "/RMII_RXD0") (class "Default")
      (node (ref "U1") (pin "33") (pinfunction "PC4_33") (pintype "passive"))
    )
    (net (code "38") (name "/RMII_RXD1") (class "Default")
      (node (ref "U1") (pin "34") (pinfunction "PC5_34") (pintype "passive"))
    )
    (net (code "39") (name "/RMII_TXD0") (class "Default") (node (ref "R22") (pin "1") (pintype "passive")))
    (net (code "40") (name "/RMII_TXD1") (class "Default") (node (ref "R23") (pin "1") (pintype "passive")))
    (net (code "41") (name "/RMII_TX_EN") (class "Default") (node (ref "R20") (pin "1") (pintype "passive")))
    (net (code "42") (name "/SENSE_RELAY_EN") (class "Default")
      (node (ref "R71") (pin "1") (pintype "passive"))
      (node (ref "U1") (pin "58") (pinfunction "PD11_58") (pintype "passive"))
    )
    (net (code "43") (name "/VCAP_1") (class "Default")
      (node (ref "C1") (pin "1") (pintype "passive"))
      (node (ref "U1") (pin "49") (pinfunction "VCAP_1_49") (pintype "passive"))
    )
    (net (code "44") (name "/VCAP_2") (class "Default")
      (node (ref "C2") (pin "1") (pintype "passive"))
      (node (ref "U1") (pin "73") (pinfunction "VCAP_2_73") (pintype "passive"))
    )
    (net (code "45") (name "/VDDA") (class "Default")
      (node (ref "C10") (pin "1") (pintype "passive"))
      (node (ref "FB1") (pin "1") (pintype "passive"))
      (node (ref "R9") (pin "1") (pintype "passive"))
      (node (ref "U1") (pin "21") (pinfunction "VREF+_21") (pintype "passive"))
      (node (ref "U1") (pin "22") (pinfunction "VDDA_22") (pintype "passive"))
    )
    (net (code "46") (name "/VS_MISO") (class "Default")
      (node (ref "R17") (pin "2") (pintype "passive"))
      (node (ref "U1") (pin "31") (pinfunction "PA6_31") (pintype "passive"))
    )
    (net (code "47") (name "/VS_MOSI") (class "Default")
      (node (ref "R16") (pin "2") (pintype "passive"))
      (node (ref "R21") (pin "2") (pintype "passive"))
    )
    (net (code "48") (name "/VS_SCK") (class "Default") (node (ref "R18") (pin "2") (pintype "passive")))
    (net (code "52") (name "/~{BATT_CS_CS}") (class "Default")
      (node (ref "R68") (pin "2") (pintype "passive"))
    )
    (net (code "53") (name "/~{BATT_CS_DR}") (class "Default")
      (node (ref "U1") (pin "95") (pinfunction "PB8_95") (pintype "passive"))
    )
    (net (code "54") (name "/~{BATT_CS_RESET}") (class "Default")
      (node (ref "R101") (pin "2") (pintype "passive"))
    )
    (net (code "55") (name "/~{CAR_CS_CS}") (class "Default")
      (node (ref "R98") (pin "2") (pintype "passive"))
    )
    (net (code "56") (name "/~{CAR_CS_DR}") (class "Default")
      (node (ref "U1") (pin "65") (pinfunction "PC8_65") (pintype "passive"))
    )
    (net (code "57") (name "/~{CAR_CS_RESET}") (class "Default")
      (node (ref "R102") (pin "2") (pintype "passive"))
    )
    (net (code "58") (name "/~{ETHERNET_RST}") (class "Default")
      (node (ref "R158") (pin "1") (pintype "passive"))
      (node (ref "U1") (pin "62") (pinfunction "PD15_62") (pintype "passive"))
    )
    (net (code "59") (name "/~{VS_CS}") (class "Default") (node (ref "R99") (pin "2") (pintype "passive")))
    (net (code "60") (name "3P3_BATT") (class "Default")
      (node (ref "C3") (pin "1") (pintype "passive"))
      (node (ref "C4") (pin "1") (pintype "passive"))
      (node (ref "C5") (pin "1") (pintype "passive"))
      (node (ref "C6") (pin "1") (pintype "passive"))
      (node (ref "C7") (pin "1") (pintype "passive"))
      (node (ref "C8") (pin "1") (pintype "passive"))
      (node (ref "C9") (pin "1") (pintype "passive"))
      (node (ref "D1") (pin "2") (pintype "passive"))
      (node (ref "FB1") (pin "2") (pintype "passive"))
      (node (ref "R1") (pin "1") (pintype "passive"))
      (node (ref "R16") (pin "1") (pintype "passive"))
      (node (ref "R17") (pin "1") (pintype "passive"))
      (node (ref "R73") (pin "1") (pintype "passive"))
      (node (ref "R8") (pin "1") (pintype "passive"))
      (node (ref "SAFE_DISABLE") (pin "2") (pintype "passive"))
      (node (ref "U1") (pin "100") (pinfunction "VDD_100") (pintype "passive"))
      (node (ref "U1") (pin "11") (pinfunction "VDD_11") (pintype "passive"))
      (node (ref "U1") (pin "19") (pinfunction "VDD_19") (pintype "passive"))
      (node (ref "U1") (pin "28") (pinfunction "VDD_28") (pintype "passive"))
      (node (ref "U1") (pin "50") (pinfunction "VDD_50") (pintype "passive"))
      (node (ref "U1") (pin "6") (pinfunction "VBAT_6") (pintype "passive"))
      (node (ref "U1") (pin "75") (pinfunction "VDD_75") (pintype "passive"))
      (node (ref "U2") (pin "1") (pinfunction "+_1") (pintype "passive"))
    )
    (net (code "61") (name "GND_BATT") (class "Default")
      (node (ref "C1") (pin "2") (pintype "passive"))
      (node (ref "C10") (pin "2") (pintype "passive"))
      (node (ref "C11") (pin "2") (pintype "passive"))
      (node (ref "C12") (pin "2") (pintype "passive"))
      (node (ref "C13") (pin "2") (pintype "passive"))
      (node (ref "C2") (pin "2") (pintype "passive"))
      (node (ref "C3") (pin "2") (pintype "passive"))
      (node (ref "C4") (pin "2") (pintype "passive"))
      (node (ref "C5") (pin "2") (pintype "passive"))
      (node (ref "C6") (pin "2") (pintype "passive"))
      (node (ref "C7") (pin "2") (pintype "passive"))
      (node (ref "C8") (pin "2") (pintype "passive"))
      (node (ref "C9") (pin "2") (pintype "passive"))
      (node (ref "J1") (pin "3") (pinfunction "GND_3") (pintype "passive"))
      (node (ref "J1") (pin "5") (pinfunction "GND_5") (pintype "passive"))
      (node (ref "Q1") (pin "2") (pinfunction "2_2") (pintype "passive"))
      (node (ref "R10") (pin "2") (pintype "passive"))
      (node (ref "R107") (pin "2") (pintype "passive"))
      (node (ref "R148") (pin "2") (pintype "passive"))
      (node (ref "R158") (pin "2") (pintype "passive"))
      (node (ref "R174") (pin "2") (pintype "passive"))
      (node (ref "R180") (pin "1") (pintype "passive"))
      (node (ref "R181") (pin "2") (pintype "passive"))
      (node (ref "R4") (pin "2") (pintype "passive"))
      (node (ref "R66") (pin "2") (pintype "passive"))
      (node (ref "R70") (pin "2") (pintype "passive"))
      (node (ref "R71") (pin "2") (pintype "passive"))
      (node (ref "R72") (pin "2") (pintype "passive"))
      (node (ref "RST1") (pin "1") (pintype "passive"))
      (node (ref "U1") (pin "10") (pinfunction "VSS_10") (pintype "passive"))
      (node (ref "U1") (pin "20") (pinfunction "VSSA_20") (pintype "passive"))
      (node (ref "U1") (pin "27") (pinfunction "VSS_27") (pintype "passive"))
      (node (ref "U1") (pin "37") (pinfunction "BOOT1_37") (pintype "passive"))
      (node (ref "U1") (pin "74") (pinfunction "VSS_74") (pintype "passive"))
      (node (ref "U1") (pin "99") (pinfunction "VSS_99") (pintype "passive"))
    )
    (net (code "62") (name "Net-(C11-Pad1)") (class "Default")
      (node (ref "C11") (pin "1") (pintype "passive"))
      (node (ref "R9") (pin "2") (pintype "passive"))
    )
    (net (code "63") (name "Net-(D18-Pad1)") (class "Default")
      (node (ref "D18") (pin "1") (pintype "passive"))
      (node (ref "R174") (pin "1") (pintype "passive"))
    )
    (net (code "64") (name "Net-(D19-Pad1)") (class "Default")
      (node (ref "D19") (pin "1") (pintype "passive"))
      (node (ref "R180") (pin "2") (pintype "passive"))
    )
    (net (code "65") (name "Net-(D20-Pad1)") (class "Default")
      (node (ref "D20") (pin "1") (pintype "passive"))
      (node (ref "R181") (pin "1") (pintype "passive"))
    )
    (net (code "66") (name "Net-(Q1-Pad1)") (class "Default")
      (node (ref "Q1") (pin "1") (pinfunction "1_1") (pintype "passive"))
      (node (ref "R7") (pin "2") (pintype "passive"))
    )
    (net (code "67") (name "Net-(U1A-PA1)") (class "Default")
      (node (ref "R13") (pin "2") (pintype "passive"))
      (node (ref "U1") (pin "24") (pinfunction "PA1_24") (pintype "passive"))
    )
    (net (code "68") (name "Net-(U1A-PA2)") (class "Default")
      (node (ref "R14") (pin "2") (pintype "passive"))
      (node (ref "U1") (pin "25") (pinfunction "PA2_25") (pintype "passive"))
    )
    (net (code "69") (name "Net-(U1A-PA5)") (class "Default")
      (node (ref "R18") (pin "1") (pintype "passive"))
      (node (ref "U1") (pin "30") (pinfunction "PA5_30") (pintype "passive"))
    )
    (net (code "70") (name "Net-(U1A-PA7)") (class "Default")
      (node (ref "R19") (pin "2") (pintype "passive"))
      (node (ref "U1") (pin "32") (pinfunction "PA7_32") (pintype "passive"))
    )
    (net (code "71") (name "Net-(U1A-PA8)") (class "Default")
      (node (ref "R99") (pin "1") (pintype "passive"))
      (node (ref "U1") (pin "67") (pinfunction "PA8_67") (pintype "passive"))
    )
    (net (code "72") (name "Net-(U1B-PB5)") (class "Default")
      (node (ref "R21") (pin "1") (pintype "passive"))
      (node (ref "U1") (pin "91") (pinfunction "PB5_91") (pintype "passive"))
    )
    (net (code "73") (name "Net-(U1B-PB7)") (class "Default")
      (node (ref "R68") (pin "1") (pintype "passive"))
      (node (ref "U1") (pin "93") (pinfunction "PB7_93") (pintype "passive"))
    )
    (net (code "74") (name "Net-(U1B-PB9)") (class "Default")
      (node (ref "R101") (pin "1") (pintype "passive"))
      (node (ref "U1") (pin "96") (pinfunction "PB9_96") (pintype "passive"))
    )
    (net (code "75") (name "Net-(U1B-PB10)") (class "Default")
      (node (ref "R104") (pin "1") (pintype "passive"))
      (node (ref "U1") (pin "47") (pinfunction "PB10_47") (pintype "passive"))
    )
    (net (code "76") (name "Net-(U1B-PB11)") (class "Default")
      (node (ref "R20") (pin "2") (pintype "passive"))
      (node (ref "U1") (pin "48") (pinfunction "PB11_48") (pintype "passive"))
    )
    (net (code "77") (name "Net-(U1B-PB12)") (class "Default")
      (node (ref "R22") (pin "2") (pintype "passive"))
      (node (ref "U1") (pin "51") (pinfunction "PB12_51") (pintype "passive"))
    )
    (net (code "78") (name "Net-(U1B-PB13)") (class "Default")
      (node (ref "R23") (pin "2") (pintype "passive"))
      (node (ref "U1") (pin "52") (pinfunction "PB13_52") (pintype "passive"))
    )
    (net (code "79") (name "Net-(U1C-PC3)") (class "Default")
      (node (ref "R15") (pin "1") (pintype "passive"))
      (node (ref "U1") (pin "18") (pinfunction "PC3_18") (pintype "passive"))
    )
    (net (code "80") (name "Net-(U1C-PC7)") (class "Default")
      (node (ref "R98") (pin "1") (pintype "passive"))
      (node (ref "U1") (pin "64") (pinfunction "PC7_64") (pintype "passive"))
    )
    (net (code "81") (name "Net-(U1C-PC9)") (class "Default")
      (node (ref "R102") (pin "1") (pintype "passive"))
      (node (ref "U1") (pin "66") (pinfunction "PC9_66") (pintype "passive"))
    )
    (net (code "82") (name "Net-(U1C-PC10)") (class "Default")
      (node (ref "R105") (pin "1") (pintype "passive"))
      (node (ref "U1") (pin "78") (pinfunction "PC10_78") (pintype "passive"))
    )
    (net (code "83") (name "Net-(U1C-PC12)") (class "Default")
      (node (ref "R106") (pin "1") (pintype "passive"))
      (node (ref "U1") (pin "80") (pinfunction "PC12_80") (pintype "passive"))
    )
    (net (code "84") (name "Net-(U1D-PD0)") (class "Default")
      (node (ref "D18") (pin "2") (pintype "passive"))
      (node (ref "U1") (pin "81") (pinfunction "PD0_81") (pintype "passive"))
    )
    (net (code "85") (name "Net-(U1D-PD1)") (class "Default")
      (node (ref "D19") (pin "2") (pintype "passive"))
      (node (ref "U1") (pin "82") (pinfunction "PD1_82") (pintype "passive"))
    )
    (net (code "86") (name "Net-(U1D-PD2)") (class "Default")
      (node (ref "D20") (pin "2") (pintype "passive"))
      (node (ref "U1") (pin "83") (pinfunction "PD2_83") (pintype "passive"))
    )
    (net (code "87") (name "Net-(U1E-PE5)") (class "Default")
      (node (ref "R66") (pin "1") (pintype "passive"))
      (node (ref "SAFE_DISABLE") (pin "1") (pintype "passive"))
      (node (ref "U1") (pin "4") (pinfunction "PE5_4") (pintype "passive"))
    )
    (net (code "88") (name "Net-(U2--)") (class "Default")
      (node (ref "D1") (pin "1") (pintype "passive"))
      (node (ref "Q1") (pin "3") (pinfunction "3_3") (pintype "passive"))
      (node (ref "U2") (pin "2") (pinfunction "-_2") (pintype "passive"))
    )
    (net (code "89") (name "unconnected-(J1-GNDdetect-Pad9)") (class "Default")
      (node (ref "J1") (pin "9") (pinfunction "GNDdetect_9") (pintype "passive+no_connect"))
    )
    (net (code "90") (name "unconnected-(J1-KEY-Pad7)") (class "Default")
      (node (ref "J1") (pin "7") (pinfunction "KEY_7") (pintype "passive+no_connect"))
    )
    (net (code "91") (name "unconnected-(U1A-PA3-Pad26)") (class "Default")
      (node (ref "U1") (pin "26") (pinfunction "PA3_26") (pintype "passive+no_connect"))
    )
    (net (code "92") (name "unconnected-(U1A-PA4-Pad29)") (class "Default")
      (node (ref "U1") (pin "29") (pinfunction "PA4_29") (pintype "passive+no_connect"))
    )
    (net (code "93") (name "unconnected-(U1A-PA9-Pad68)") (class "Default")
      (node (ref "U1") (pin "68") (pinfunction "PA9_68") (pintype "passive+no_connect"))
    )
    (net (code "94") (name "unconnected-(U1A-PA10-Pad69)") (class "Default")
      (node (ref "U1") (pin "69") (pinfunction "PA10_69") (pintype "passive+no_connect"))
    )
    (net (code "95") (name "unconnected-(U1A-PA11-Pad70)") (class "Default")
      (node (ref "U1") (pin "70") (pinfunction "PA11_70") (pintype "passive+no_connect"))
    )
    (net (code "96") (name "unconnected-(U1A-PA12-Pad71)") (class "Default")
      (node (ref "U1") (pin "71") (pinfunction "PA12_71") (pintype "passive+no_connect"))
    )
    (net (code "97") (name "unconnected-(U1B-PB6-Pad92)") (class "Default")
      (node (ref "U1") (pin "92") (pinfunction "PB6_92") (pintype "passive+no_connect"))
    )
    (net (code "98") (name "unconnected-(U1B-PB14-Pad53)") (class "Default")
      (node (ref "U1") (pin "53") (pinfunction "PB14_53") (pintype "passive+no_connect"))
    )
    (net (code "99") (name "unconnected-(U1B-PB15-Pad54)") (class "Default")
      (node (ref "U1") (pin "54") (pinfunction "PB15_54") (pintype "passive+no_connect"))
    )
    (net (code "100") (name "unconnected-(U1C-PC0-Pad15)") (class "Default")
      (node (ref "U1") (pin "15") (pinfunction "PC0_15") (pintype "passive+no_connect"))
    )
    (net (code "101") (name "unconnected-(U1C-PC6-Pad63)") (class "Default")
      (node (ref "U1") (pin "63") (pinfunction "PC6_63") (pintype "passive+no_connect"))
    )
    (net (code "102") (name "unconnected-(U1C-PC13-Pad7)") (class "Default")
      (node (ref "U1") (pin "7") (pinfunction "PC13_7") (pintype "passive+no_connect"))
    )
    (net (code "103") (name "unconnected-(U1D-PD3-Pad84)") (class "Default")
      (node (ref "U1") (pin "84") (pinfunction "PD3_84") (pintype "passive+no_connect"))
    )
    (net (code "104") (name "unconnected-(U1D-PD4-Pad85)") (class "Default")
      (node (ref "U1") (pin "85") (pinfunction "PD4_85") (pintype "passive+no_connect"))
    )
    (net (code "105") (name "unconnected-(U1D-PD6-Pad87)") (class "Default")
      (node (ref "U1") (pin "87") (pinfunction "PD6_87") (pintype "passive+no_connect"))
    )
    (net (code "106") (name "unconnected-(U1D-PD7-Pad88)") (class "Default")
      (node (ref "U1") (pin "88") (pinfunction "PD7_88") (pintype "passive+no_connect"))
    )
    (net (code "107") (name "unconnected-(U1D-PD12-Pad59)") (class "Default")
      (node (ref "U1") (pin "59") (pinfunction "PD12_59") (pintype "passive+no_connect"))
    )
    (net (code "108") (name "unconnected-(U1D-PD13-Pad60)") (class "Default")
      (node (ref "U1") (pin "60") (pinfunction "PD13_60") (pintype "passive+no_connect"))
    )
    (net (code "109") (name "unconnected-(U1E-PE0-Pad97)") (class "Default")
      (node (ref "U1") (pin "97") (pinfunction "PE0_97") (pintype "passive+no_connect"))
    )
    (net (code "110") (name "unconnected-(U1E-PE1-Pad98)") (class "Default")
      (node (ref "U1") (pin "98") (pinfunction "PE1_98") (pintype "passive+no_connect"))
    )
    (net (code "111") (name "unconnected-(U1E-PE3-Pad2)") (class "Default")
      (node (ref "U1") (pin "2") (pinfunction "PE3_2") (pintype "passive+no_connect"))
    )
    (net (code "112") (name "unconnected-(U1E-PE4-Pad3)") (class "Default")
      (node (ref "U1") (pin "3") (pinfunction "PE4_3") (pintype "passive+no_connect"))
    )
    (net (code "113") (name "unconnected-(U1E-PE6-Pad5)") (class "Default")
      (node (ref "U1") (pin "5") (pinfunction "PE6_5") (pintype "passive+no_connect"))
    )
    (net (code "114") (name "unconnected-(U1E-PE7-Pad38)") (class "Default")
      (node (ref "U1") (pin "38") (pinfunction "PE7_38") (pintype "passive+no_connect"))
    )
    (net (code "115") (name "unconnected-(U1E-PE8-Pad39)") (class "Default")
      (node (ref "U1") (pin "39") (pinfunction "PE8_39") (pintype "passive+no_connect"))
    )
    (net (code "116") (name "unconnected-(U1E-PE9-Pad40)") (class "Default")
      (node (ref "U1") (pin "40") (pinfunction "PE9_40") (pintype "passive+no_connect"))
    )
    (net (code "117") (name "unconnected-(U1E-PE10-Pad41)") (class "Default")
      (node (ref "U1") (pin "41") (pinfunction "PE10_41") (pintype "passive+no_connect"))
    )
    (net (code "118") (name "unconnected-(U1E-PE11-Pad42)") (class "Default")
      (node (ref "U1") (pin "42") (pinfunction "PE11_42") (pintype "passive+no_connect"))
    )
    (net (code "119") (name "unconnected-(U1E-PE12-Pad43)") (class "Default")
      (node (ref "U1") (pin "43") (pinfunction "PE12_43") (pintype "passive+no_connect"))
    )
    (net (code "120") (name "unconnected-(U1E-PE13-Pad44)") (class "Default")
      (node (ref "U1") (pin "44") (pinfunction "PE13_44") (pintype "passive+no_connect"))
    )
    (net (code "121") (name "unconnected-(U1E-PE14-Pad45)") (class "Default")
      (node (ref "U1") (pin "45") (pinfunction "PE14_45") (pintype "passive+no_connect"))
    )
    (net (code "122") (name "unconnected-(U1E-PE15-Pad46)") (class "Default")
      (node (ref "U1") (pin "46") (pinfunction "PE15_46") (pintype "passive+no_connect"))
    )
    (net (code "123") (name "unconnected-(U1G-NJTRST-Pad90)") (class "Default")
      (node (ref "U1") (pin "90") (pinfunction "NJTRST_90") (pintype "passive+no_connect"))
    )
    (net (code "124") (name "unconnected-(U1G-OSC32_IN-Pad8)") (class "Default")
      (node (ref "U1") (pin "8") (pinfunction "OSC32_IN_8") (pintype "passive+no_connect"))
    )
    (net (code "125") (name "unconnected-(U1G-OSC32_OUT-Pad9)") (class "Default")
      (node (ref "U1") (pin "9") (pinfunction "OSC32_OUT_9") (pintype "passive+no_connect"))
    )
    (net (code "126") (name "unconnected-(U1G-WKUP-Pad23)") (class "Default")
      (node (ref "U1") (pin "23") (pinfunction "WKUP_23") (pintype "passive+no_connect"))
    )
  )
)
